# G785X.net
KiCad netlist of a schematic drawn in EAGLE
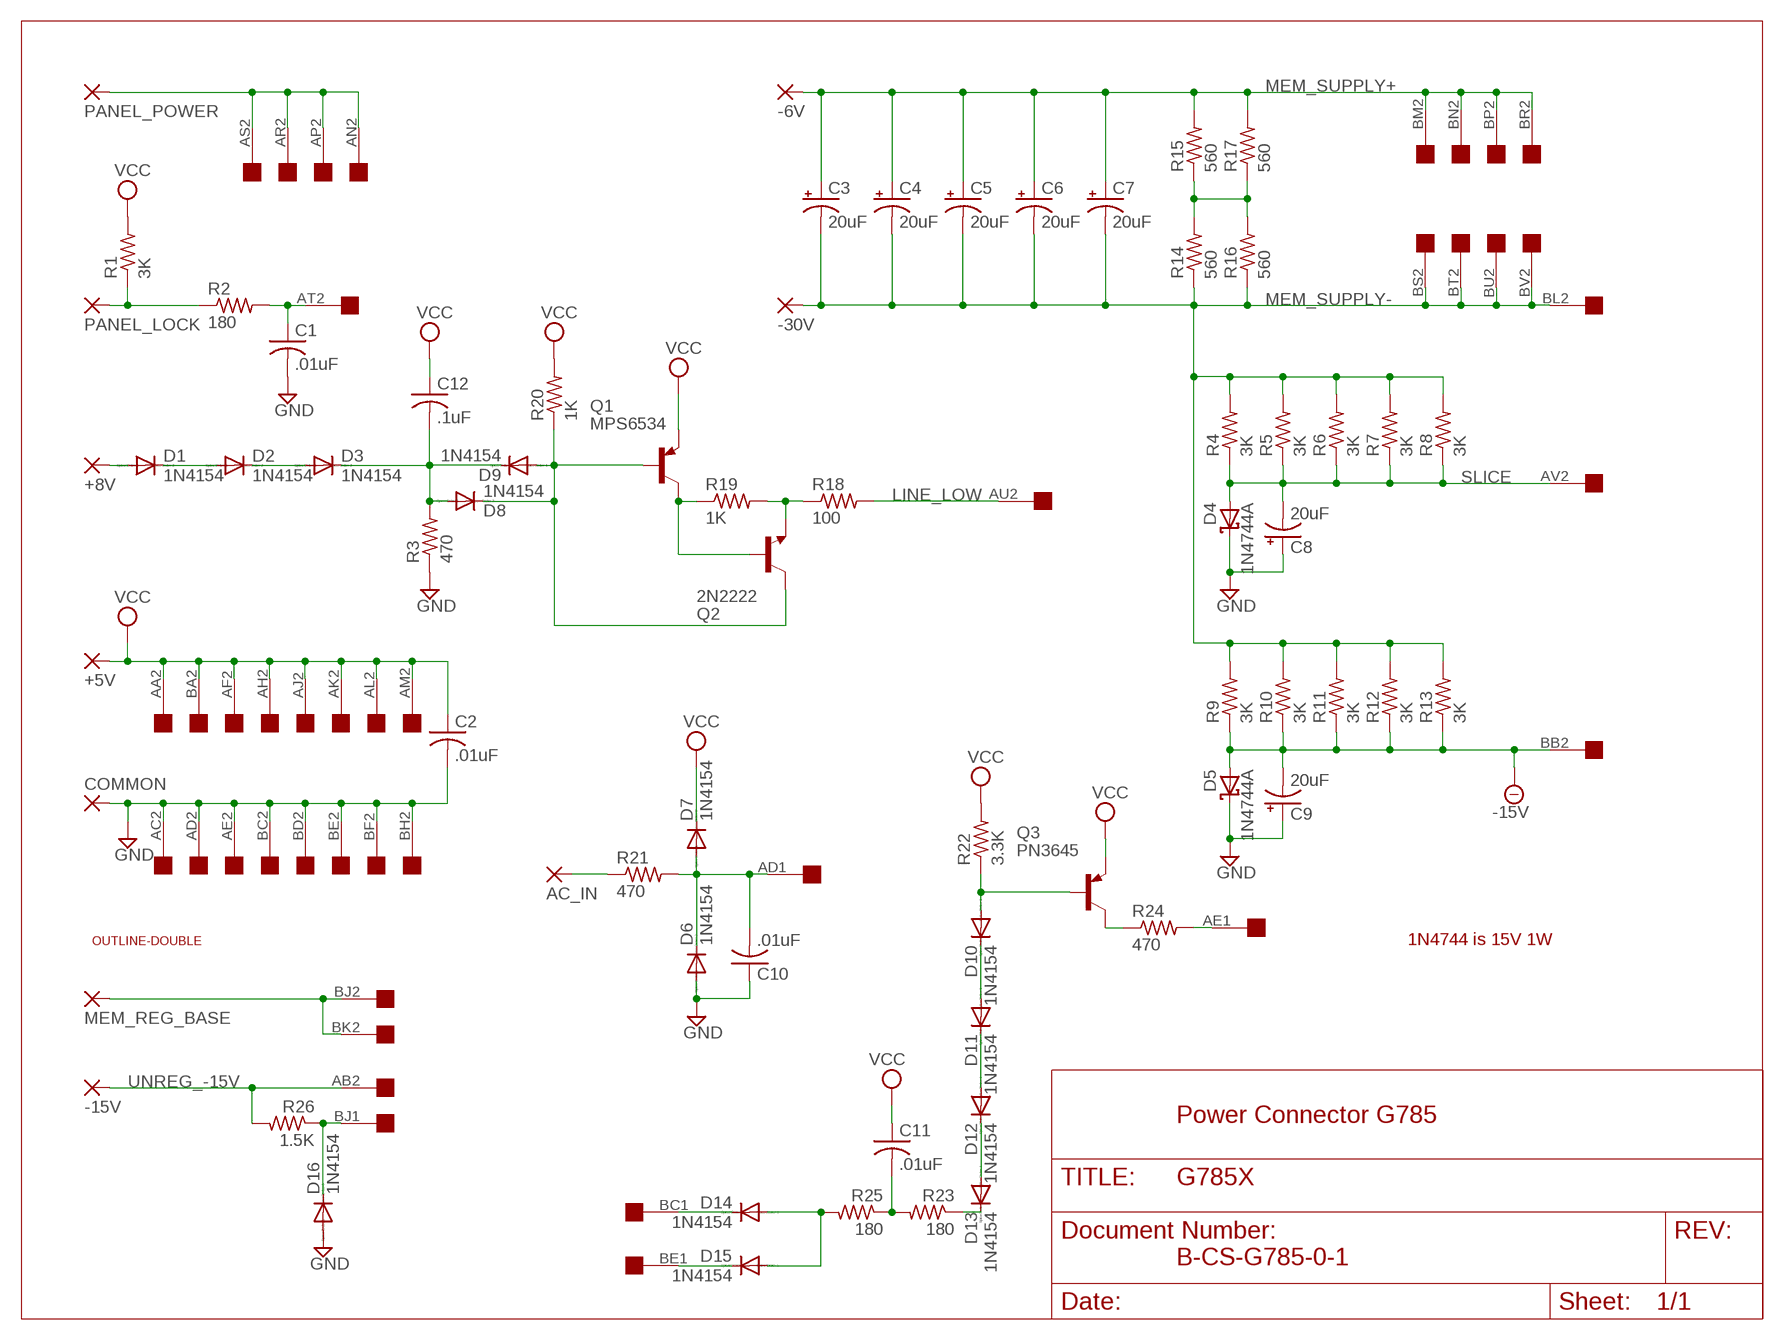
[diagram p0: schematic, sheet 1]

(export (version "E")
  (design (tool "Eeschema 10.0.6"))
  (components
    (comp (ref "+5V")
      (value "3,81/1,4")
      (footprint "eagle-import:3,81_1,4")
      (libsource (lib "eagle-import") (part "3,81/1,4"))
    )
    (comp (ref "+8V")
      (value "3,81/1,4")
      (footprint "eagle-import:3,81_1,4")
      (libsource (lib "eagle-import") (part "3,81/1,4"))
    )
    (comp (ref "-6V")
      (value "3,81/1,4")
      (footprint "eagle-import:3,81_1,4")
      (libsource (lib "eagle-import") (part "3,81/1,4"))
    )
    (comp (ref "-15V")
      (value "3,81/1,4")
      (footprint "eagle-import:3,81_1,4")
      (libsource (lib "eagle-import") (part "3,81/1,4"))
    )
    (comp (ref "-30V")
      (value "3,81/1,4")
      (footprint "eagle-import:3,81_1,4")
      (libsource (lib "eagle-import") (part "3,81/1,4"))
    )
    (comp (ref "AC_IN")
      (value "3,81/1,4")
      (footprint "eagle-import:3,81_1,4")
      (libsource (lib "eagle-import") (part "3,81/1,4"))
    )
    (comp (ref "C1")
      (value ".01uF")
      (footprint "eagle-import:C050-025X075")
      (libsource (lib "eagle-import") (part "C-US050-025X075"))
    )
    (comp (ref "C2")
      (value ".01uF")
      (footprint "eagle-import:C050-025X075")
      (libsource (lib "eagle-import") (part "C-US050-025X075"))
    )
    (comp (ref "C3")
      (value "20uF")
      (footprint "eagle-import:E25-9")
      (libsource (lib "eagle-import") (part "CPOL-USE25-9AXIAL"))
    )
    (comp (ref "C4")
      (value "20uF")
      (footprint "eagle-import:E25-9")
      (libsource (lib "eagle-import") (part "CPOL-USE25-9AXIAL"))
    )
    (comp (ref "C5")
      (value "20uF")
      (footprint "eagle-import:E25-9")
      (libsource (lib "eagle-import") (part "CPOL-USE25-9AXIAL"))
    )
    (comp (ref "C6")
      (value "20uF")
      (footprint "eagle-import:E25-9")
      (libsource (lib "eagle-import") (part "CPOL-USE25-9AXIAL"))
    )
    (comp (ref "C7")
      (value "20uF")
      (footprint "eagle-import:E25-9")
      (libsource (lib "eagle-import") (part "CPOL-USE25-9AXIAL"))
    )
    (comp (ref "C8")
      (value "20uF")
      (footprint "eagle-import:E25-9")
      (libsource (lib "eagle-import") (part "CPOL-USE25-9AXIAL"))
    )
    (comp (ref "C9")
      (value "20uF")
      (footprint "eagle-import:E25-9")
      (libsource (lib "eagle-import") (part "CPOL-USE25-9AXIAL"))
    )
    (comp (ref "C10")
      (value ".01uF")
      (footprint "eagle-import:C050-025X075")
      (libsource (lib "eagle-import") (part "C-US050-025X075"))
    )
    (comp (ref "C11")
      (value ".01uF")
      (footprint "eagle-import:C050-025X075")
      (libsource (lib "eagle-import") (part "C-US050-025X075"))
    )
    (comp (ref "C12")
      (value ".1uF")
      (footprint "eagle-import:C102-043X133")
      (libsource (lib "eagle-import") (part "C-US102-043X133"))
    )
    (comp (ref "COMMON")
      (value "3,81/1,4")
      (footprint "eagle-import:3,81_1,4")
      (libsource (lib "eagle-import") (part "3,81/1,4"))
    )
    (comp (ref "D1")
      (value "1N4154")
      (footprint "eagle-import:DO35-10")
      (libsource (lib "eagle-import") (part "1N4148DO35-10"))
    )
    (comp (ref "D2")
      (value "1N4154")
      (footprint "eagle-import:DO35-10")
      (libsource (lib "eagle-import") (part "1N4148DO35-10"))
    )
    (comp (ref "D3")
      (value "1N4154")
      (footprint "eagle-import:DO35-10")
      (libsource (lib "eagle-import") (part "1N4148DO35-10"))
    )
    (comp (ref "D4")
      (value "1N4744A")
      (footprint "eagle-import:DO35-10")
      (libsource (lib "eagle-import") (part "BAT42"))
    )
    (comp (ref "D5")
      (value "1N4744A")
      (footprint "eagle-import:DO35-10")
      (libsource (lib "eagle-import") (part "BAT42"))
    )
    (comp (ref "D6")
      (value "1N4154")
      (footprint "eagle-import:DO35-10")
      (libsource (lib "eagle-import") (part "1N4148DO35-10"))
    )
    (comp (ref "D7")
      (value "1N4154")
      (footprint "eagle-import:DO35-10")
      (libsource (lib "eagle-import") (part "1N4148DO35-10"))
    )
    (comp (ref "D8")
      (value "1N4154")
      (footprint "eagle-import:DO35-10")
      (libsource (lib "eagle-import") (part "1N4148DO35-10"))
    )
    (comp (ref "D9")
      (value "1N4154")
      (footprint "eagle-import:DO35-10")
      (libsource (lib "eagle-import") (part "1N4148DO35-10"))
    )
    (comp (ref "D10")
      (value "1N4154")
      (footprint "eagle-import:DO35-10")
      (libsource (lib "eagle-import") (part "1N4148DO35-10"))
    )
    (comp (ref "D11")
      (value "1N4154")
      (footprint "eagle-import:DO35-10")
      (libsource (lib "eagle-import") (part "1N4148DO35-10"))
    )
    (comp (ref "D12")
      (value "1N4154")
      (footprint "eagle-import:DO35-10")
      (libsource (lib "eagle-import") (part "1N4148DO35-10"))
    )
    (comp (ref "D13")
      (value "1N4154")
      (footprint "eagle-import:DO35-10")
      (libsource (lib "eagle-import") (part "1N4148DO35-10"))
    )
    (comp (ref "D14")
      (value "1N4154")
      (footprint "eagle-import:DO35-10")
      (libsource (lib "eagle-import") (part "1N4148DO35-10"))
    )
    (comp (ref "D15")
      (value "1N4154")
      (footprint "eagle-import:DO35-10")
      (libsource (lib "eagle-import") (part "1N4148DO35-10"))
    )
    (comp (ref "D16")
      (value "1N4154")
      (footprint "eagle-import:DO35-10")
      (libsource (lib "eagle-import") (part "1N4148DO35-10"))
    )
    (comp (ref "MEM_REG_BASE")
      (value "3,81/1,4")
      (footprint "eagle-import:3,81_1,4")
      (libsource (lib "eagle-import") (part "3,81/1,4"))
    )
    (comp (ref "PANEL_LOCK")
      (value "3,81/1,4")
      (footprint "eagle-import:3,81_1,4")
      (libsource (lib "eagle-import") (part "3,81/1,4"))
    )
    (comp (ref "PANEL_POWER")
      (value "3,81/1,4")
      (footprint "eagle-import:3,81_1,4")
      (libsource (lib "eagle-import") (part "3,81/1,4"))
    )
    (comp (ref "Q1")
      (value "MPS6534")
      (footprint "eagle-import:TO39")
      (libsource (lib "eagle-import") (part "2N2904"))
    )
    (comp (ref "Q2")
      (value "2N2222")
      (footprint "eagle-import:TO5")
      (libsource (lib "eagle-import") (part "2N2219"))
    )
    (comp (ref "Q3")
      (value "PN3645")
      (footprint "eagle-import:TO39")
      (libsource (lib "eagle-import") (part "2N2904"))
    )
    (comp (ref "R1")
      (value "3K")
      (footprint "eagle-import:0207_10")
      (libsource (lib "eagle-import") (part "R-US_0207/10"))
    )
    (comp (ref "R2")
      (value "180")
      (footprint "eagle-import:0207_10")
      (libsource (lib "eagle-import") (part "R-US_0207/10"))
    )
    (comp (ref "R3")
      (value "470")
      (footprint "eagle-import:0207_10")
      (libsource (lib "eagle-import") (part "R-US_0207/10"))
    )
    (comp (ref "R4")
      (value "3K")
      (footprint "eagle-import:0207_10")
      (libsource (lib "eagle-import") (part "R-US_0207/10"))
    )
    (comp (ref "R5")
      (value "3K")
      (footprint "eagle-import:0207_10")
      (libsource (lib "eagle-import") (part "R-US_0207/10"))
    )
    (comp (ref "R6")
      (value "3K")
      (footprint "eagle-import:0207_10")
      (libsource (lib "eagle-import") (part "R-US_0207/10"))
    )
    (comp (ref "R7")
      (value "3K")
      (footprint "eagle-import:0207_10")
      (libsource (lib "eagle-import") (part "R-US_0207/10"))
    )
    (comp (ref "R8")
      (value "3K")
      (footprint "eagle-import:0207_10")
      (libsource (lib "eagle-import") (part "R-US_0207/10"))
    )
    (comp (ref "R9")
      (value "3K")
      (footprint "eagle-import:0207_10")
      (libsource (lib "eagle-import") (part "R-US_0207/10"))
    )
    (comp (ref "R10")
      (value "3K")
      (footprint "eagle-import:0207_10")
      (libsource (lib "eagle-import") (part "R-US_0207/10"))
    )
    (comp (ref "R11")
      (value "3K")
      (footprint "eagle-import:0207_10")
      (libsource (lib "eagle-import") (part "R-US_0207/10"))
    )
    (comp (ref "R12")
      (value "3K")
      (footprint "eagle-import:0207_10")
      (libsource (lib "eagle-import") (part "R-US_0207/10"))
    )
    (comp (ref "R13")
      (value "3K")
      (footprint "eagle-import:0207_10")
      (libsource (lib "eagle-import") (part "R-US_0207/10"))
    )
    (comp (ref "R14")
      (value "560")
      (footprint "eagle-import:0207_10")
      (libsource (lib "eagle-import") (part "R-US_0207/10"))
    )
    (comp (ref "R15")
      (value "560")
      (footprint "eagle-import:0207_10")
      (libsource (lib "eagle-import") (part "R-US_0207/10"))
    )
    (comp (ref "R16")
      (value "560")
      (footprint "eagle-import:0207_10")
      (libsource (lib "eagle-import") (part "R-US_0207/10"))
    )
    (comp (ref "R17")
      (value "560")
      (footprint "eagle-import:0207_10")
      (libsource (lib "eagle-import") (part "R-US_0207/10"))
    )
    (comp (ref "R18")
      (value "100")
      (footprint "eagle-import:0207_10")
      (libsource (lib "eagle-import") (part "R-US_0207/10"))
    )
    (comp (ref "R19")
      (value "1K")
      (footprint "eagle-import:0207_10")
      (libsource (lib "eagle-import") (part "R-US_0207/10"))
    )
    (comp (ref "R20")
      (value "1K")
      (footprint "eagle-import:0207_10")
      (libsource (lib "eagle-import") (part "R-US_0207/10"))
    )
    (comp (ref "R21")
      (value "470")
      (footprint "eagle-import:0207_10")
      (libsource (lib "eagle-import") (part "R-US_0207/10"))
    )
    (comp (ref "R22")
      (value "3.3K")
      (footprint "eagle-import:0207_10")
      (libsource (lib "eagle-import") (part "R-US_0207/10"))
    )
    (comp (ref "R23")
      (value "180")
      (footprint "eagle-import:0207_10")
      (libsource (lib "eagle-import") (part "R-US_0207/10"))
    )
    (comp (ref "R24")
      (value "470")
      (footprint "eagle-import:0207_10")
      (libsource (lib "eagle-import") (part "R-US_0207/10"))
    )
    (comp (ref "R25")
      (value "180")
      (footprint "eagle-import:0207_10")
      (libsource (lib "eagle-import") (part "R-US_0207/10"))
    )
    (comp (ref "R26")
      (value "1.5K")
      (footprint "eagle-import:0207_10")
      (libsource (lib "eagle-import") (part "R-US_0207/10"))
    )
    (comp (ref "U$1")
      (value "DOUBLE")
      (footprint "eagle-import:EDGE-CON4")
      (libsource (lib "eagle-import") (part "DOUBLE"))
    )
    (comp (ref "U$2")
      (value "OUTLINE-DOUBLE")
      (footprint "eagle-import:DOUBLE")
      (libsource (lib "eagle-import") (part "OUTLINE-DOUBLE"))
    )
  )
  (nets
    (net (code "1") (name "-15V") (class "Default")
      (node (ref "C9") (pin "-") (pinfunction "-_-") (pintype "passive"))
      (node (ref "D5") (pin "A") (pinfunction "A_A") (pintype "passive"))
      (node (ref "R10") (pin "1") (pinfunction "1_1") (pintype "passive"))
      (node (ref "R11") (pin "1") (pinfunction "1_1") (pintype "passive"))
      (node (ref "R12") (pin "1") (pinfunction "1_1") (pintype "passive"))
      (node (ref "R13") (pin "1") (pinfunction "1_1") (pintype "passive"))
      (node (ref "R9") (pin "1") (pinfunction "1_1") (pintype "passive"))
      (node (ref "U$1") (pin "BB2") (pinfunction "1_BB2") (pintype "bidirectional"))
    )
    (net (code "2") (name "/LINE_LOW") (class "Default")
      (node (ref "R18") (pin "2") (pinfunction "2_2") (pintype "passive"))
      (node (ref "U$1") (pin "AU2") (pinfunction "1_AU2") (pintype "bidirectional"))
    )
    (net (code "3") (name "/MEM_SUPPLY+") (class "Default")
      (node (ref "-6V") (pin "1") (pinfunction "P_1") (pintype "passive"))
      (node (ref "C3") (pin "+") (pinfunction "+_+") (pintype "passive"))
      (node (ref "C4") (pin "+") (pinfunction "+_+") (pintype "passive"))
      (node (ref "C5") (pin "+") (pinfunction "+_+") (pintype "passive"))
      (node (ref "C6") (pin "+") (pinfunction "+_+") (pintype "passive"))
      (node (ref "C7") (pin "+") (pinfunction "+_+") (pintype "passive"))
      (node (ref "R15") (pin "2") (pinfunction "2_2") (pintype "passive"))
      (node (ref "R17") (pin "2") (pinfunction "2_2") (pintype "passive"))
      (node (ref "U$1") (pin "BM2") (pinfunction "1_BM2") (pintype "bidirectional"))
      (node (ref "U$1") (pin "BN2") (pinfunction "1_BN2") (pintype "bidirectional"))
      (node (ref "U$1") (pin "BP2") (pinfunction "1_BP2") (pintype "bidirectional"))
      (node (ref "U$1") (pin "BR2") (pinfunction "1_BR2") (pintype "bidirectional"))
    )
    (net (code "4") (name "/MEM_SUPPLY-") (class "Default")
      (node (ref "-30V") (pin "1") (pinfunction "P_1") (pintype "passive"))
      (node (ref "C3") (pin "-") (pinfunction "-_-") (pintype "passive"))
      (node (ref "C4") (pin "-") (pinfunction "-_-") (pintype "passive"))
      (node (ref "C5") (pin "-") (pinfunction "-_-") (pintype "passive"))
      (node (ref "C6") (pin "-") (pinfunction "-_-") (pintype "passive"))
      (node (ref "C7") (pin "-") (pinfunction "-_-") (pintype "passive"))
      (node (ref "R10") (pin "2") (pinfunction "2_2") (pintype "passive"))
      (node (ref "R11") (pin "2") (pinfunction "2_2") (pintype "passive"))
      (node (ref "R12") (pin "2") (pinfunction "2_2") (pintype "passive"))
      (node (ref "R13") (pin "2") (pinfunction "2_2") (pintype "passive"))
      (node (ref "R14") (pin "1") (pinfunction "1_1") (pintype "passive"))
      (node (ref "R16") (pin "1") (pinfunction "1_1") (pintype "passive"))
      (node (ref "R4") (pin "2") (pinfunction "2_2") (pintype "passive"))
      (node (ref "R5") (pin "2") (pinfunction "2_2") (pintype "passive"))
      (node (ref "R6") (pin "2") (pinfunction "2_2") (pintype "passive"))
      (node (ref "R7") (pin "2") (pinfunction "2_2") (pintype "passive"))
      (node (ref "R8") (pin "2") (pinfunction "2_2") (pintype "passive"))
      (node (ref "R9") (pin "2") (pinfunction "2_2") (pintype "passive"))
      (node (ref "U$1") (pin "BL2") (pinfunction "1_BL2") (pintype "bidirectional"))
      (node (ref "U$1") (pin "BS2") (pinfunction "1_BS2") (pintype "bidirectional"))
      (node (ref "U$1") (pin "BT2") (pinfunction "1_BT2") (pintype "bidirectional"))
      (node (ref "U$1") (pin "BU2") (pinfunction "1_BU2") (pintype "bidirectional"))
      (node (ref "U$1") (pin "BV2") (pinfunction "1_BV2") (pintype "bidirectional"))
    )
    (net (code "5") (name "/SLICE") (class "Default")
      (node (ref "C8") (pin "-") (pinfunction "-_-") (pintype "passive"))
      (node (ref "D4") (pin "A") (pinfunction "A_A") (pintype "passive"))
      (node (ref "R4") (pin "1") (pinfunction "1_1") (pintype "passive"))
      (node (ref "R5") (pin "1") (pinfunction "1_1") (pintype "passive"))
      (node (ref "R6") (pin "1") (pinfunction "1_1") (pintype "passive"))
      (node (ref "R7") (pin "1") (pinfunction "1_1") (pintype "passive"))
      (node (ref "R8") (pin "1") (pinfunction "1_1") (pintype "passive"))
      (node (ref "U$1") (pin "AV2") (pinfunction "1_AV2") (pintype "bidirectional"))
    )
    (net (code "6") (name "/UNREG_-15V") (class "Default")
      (node (ref "-15V") (pin "1") (pinfunction "P_1") (pintype "passive"))
      (node (ref "R26") (pin "2") (pinfunction "2_2") (pintype "passive"))
      (node (ref "U$1") (pin "AB2") (pinfunction "1_AB2") (pintype "bidirectional"))
    )
    (net (code "7") (name "GND") (class "Default")
      (node (ref "C1") (pin "2") (pinfunction "2_2") (pintype "passive"))
      (node (ref "C10") (pin "1") (pinfunction "1_1") (pintype "passive"))
      (node (ref "C2") (pin "2") (pinfunction "2_2") (pintype "passive"))
      (node (ref "C8") (pin "+") (pinfunction "+_+") (pintype "passive"))
      (node (ref "C9") (pin "+") (pinfunction "+_+") (pintype "passive"))
      (node (ref "COMMON") (pin "1") (pinfunction "P_1") (pintype "passive"))
      (node (ref "D16") (pin "A") (pinfunction "A_A") (pintype "passive"))
      (node (ref "D4") (pin "C") (pinfunction "C_C") (pintype "passive"))
      (node (ref "D5") (pin "C") (pinfunction "C_C") (pintype "passive"))
      (node (ref "D6") (pin "A") (pinfunction "A_A") (pintype "passive"))
      (node (ref "R3") (pin "1") (pinfunction "1_1") (pintype "passive"))
      (node (ref "U$1") (pin "AC2") (pinfunction "1_AC2") (pintype "bidirectional"))
      (node (ref "U$1") (pin "AD2") (pinfunction "1_AD2") (pintype "bidirectional"))
      (node (ref "U$1") (pin "AE2") (pinfunction "1_AE2") (pintype "bidirectional"))
      (node (ref "U$1") (pin "BC2") (pinfunction "1_BC2") (pintype "bidirectional"))
      (node (ref "U$1") (pin "BD2") (pinfunction "1_BD2") (pintype "bidirectional"))
      (node (ref "U$1") (pin "BE2") (pinfunction "1_BE2") (pintype "bidirectional"))
      (node (ref "U$1") (pin "BF2") (pinfunction "1_BF2") (pintype "bidirectional"))
      (node (ref "U$1") (pin "BH2") (pinfunction "1_BH2") (pintype "bidirectional"))
    )
    (net (code "8") (name "Net-(+8V-P)") (class "Default")
      (node (ref "+8V") (pin "1") (pinfunction "P_1") (pintype "passive"))
      (node (ref "D1") (pin "A") (pinfunction "A_A") (pintype "passive"))
    )
    (net (code "9") (name "Net-(AC_IN-P)") (class "Default")
      (node (ref "AC_IN") (pin "1") (pinfunction "P_1") (pintype "passive"))
      (node (ref "R21") (pin "1") (pinfunction "1_1") (pintype "passive"))
    )
    (net (code "10") (name "Net-(C11-Pad2)") (class "Default")
      (node (ref "C11") (pin "2") (pinfunction "2_2") (pintype "passive"))
      (node (ref "R23") (pin "2") (pinfunction "2_2") (pintype "passive"))
      (node (ref "R25") (pin "1") (pinfunction "1_1") (pintype "passive"))
    )
    (net (code "11") (name "Net-(C12-Pad2)") (class "Default")
      (node (ref "C12") (pin "2") (pinfunction "2_2") (pintype "passive"))
      (node (ref "D3") (pin "C") (pinfunction "C_C") (pintype "passive"))
      (node (ref "D8") (pin "A") (pinfunction "A_A") (pintype "passive"))
      (node (ref "D9") (pin "C") (pinfunction "C_C") (pintype "passive"))
      (node (ref "R3") (pin "2") (pinfunction "2_2") (pintype "passive"))
    )
    (net (code "12") (name "Net-(D1-PadC)") (class "Default")
      (node (ref "D1") (pin "C") (pinfunction "C_C") (pintype "passive"))
      (node (ref "D2") (pin "A") (pinfunction "A_A") (pintype "passive"))
    )
    (net (code "13") (name "Net-(D2-PadC)") (class "Default")
      (node (ref "D2") (pin "C") (pinfunction "C_C") (pintype "passive"))
      (node (ref "D3") (pin "A") (pinfunction "A_A") (pintype "passive"))
    )
    (net (code "14") (name "Net-(D10-PadC)") (class "Default")
      (node (ref "D10") (pin "C") (pinfunction "C_C") (pintype "passive"))
      (node (ref "D11") (pin "A") (pinfunction "A_A") (pintype "passive"))
    )
    (net (code "15") (name "Net-(D11-PadC)") (class "Default")
      (node (ref "D11") (pin "C") (pinfunction "C_C") (pintype "passive"))
      (node (ref "D12") (pin "A") (pinfunction "A_A") (pintype "passive"))
    )
    (net (code "16") (name "Net-(D12-PadC)") (class "Default")
      (node (ref "D12") (pin "C") (pinfunction "C_C") (pintype "passive"))
      (node (ref "D13") (pin "A") (pinfunction "A_A") (pintype "passive"))
    )
    (net (code "17") (name "Net-(D13-PadC)") (class "Default")
      (node (ref "D13") (pin "C") (pinfunction "C_C") (pintype "passive"))
      (node (ref "R23") (pin "1") (pinfunction "1_1") (pintype "passive"))
    )
    (net (code "18") (name "Net-(D14-PadA)") (class "Default")
      (node (ref "D14") (pin "A") (pinfunction "A_A") (pintype "passive"))
      (node (ref "D15") (pin "A") (pinfunction "A_A") (pintype "passive"))
      (node (ref "R25") (pin "2") (pinfunction "2_2") (pintype "passive"))
    )
    (net (code "19") (name "Net-(MEM_REG_BASE-P)") (class "Default")
      (node (ref "MEM_REG_BASE") (pin "1") (pinfunction "P_1") (pintype "passive"))
      (node (ref "U$1") (pin "BJ2") (pinfunction "1_BJ2") (pintype "bidirectional"))
      (node (ref "U$1") (pin "BK2") (pinfunction "1_BK2") (pintype "bidirectional"))
    )
    (net (code "20") (name "Net-(PANEL_LOCK-P)") (class "Default")
      (node (ref "PANEL_LOCK") (pin "1") (pinfunction "P_1") (pintype "passive"))
      (node (ref "R1") (pin "1") (pinfunction "1_1") (pintype "passive"))
      (node (ref "R2") (pin "1") (pinfunction "1_1") (pintype "passive"))
    )
    (net (code "21") (name "Net-(PANEL_POWER-P)") (class "Default")
      (node (ref "PANEL_POWER") (pin "1") (pinfunction "P_1") (pintype "passive"))
      (node (ref "U$1") (pin "AN2") (pinfunction "1_AN2") (pintype "bidirectional"))
      (node (ref "U$1") (pin "AP2") (pinfunction "1_AP2") (pintype "bidirectional"))
      (node (ref "U$1") (pin "AR2") (pinfunction "1_AR2") (pintype "bidirectional"))
      (node (ref "U$1") (pin "AS2") (pinfunction "1_AS2") (pintype "bidirectional"))
    )
    (net (code "22") (name "Net-(Q1-B)") (class "Default")
      (node (ref "D8") (pin "C") (pinfunction "C_C") (pintype "passive"))
      (node (ref "D9") (pin "A") (pinfunction "A_A") (pintype "passive"))
      (node (ref "Q1") (pin "2") (pinfunction "B_2") (pintype "passive"))
      (node (ref "Q2") (pin "3") (pinfunction "C_3") (pintype "passive"))
      (node (ref "R20") (pin "1") (pinfunction "1_1") (pintype "passive"))
    )
    (net (code "23") (name "Net-(Q1-C)") (class "Default")
      (node (ref "Q1") (pin "3") (pinfunction "C_3") (pintype "passive"))
      (node (ref "Q2") (pin "2") (pinfunction "B_2") (pintype "passive"))
      (node (ref "R19") (pin "1") (pinfunction "1_1") (pintype "passive"))
    )
    (net (code "24") (name "Net-(Q2-E)") (class "Default")
      (node (ref "Q2") (pin "1") (pinfunction "E_1") (pintype "passive"))
      (node (ref "R18") (pin "1") (pinfunction "1_1") (pintype "passive"))
      (node (ref "R19") (pin "2") (pinfunction "2_2") (pintype "passive"))
    )
    (net (code "25") (name "Net-(Q3-B)") (class "Default")
      (node (ref "D10") (pin "A") (pinfunction "A_A") (pintype "passive"))
      (node (ref "Q3") (pin "2") (pinfunction "B_2") (pintype "passive"))
      (node (ref "R22") (pin "1") (pinfunction "1_1") (pintype "passive"))
    )
    (net (code "26") (name "Net-(Q3-C)") (class "Default")
      (node (ref "Q3") (pin "3") (pinfunction "C_3") (pintype "passive"))
      (node (ref "R24") (pin "1") (pinfunction "1_1") (pintype "passive"))
    )
    (net (code "27") (name "Net-(R14-Pad2)") (class "Default")
      (node (ref "R14") (pin "2") (pinfunction "2_2") (pintype "passive"))
      (node (ref "R15") (pin "1") (pinfunction "1_1") (pintype "passive"))
      (node (ref "R16") (pin "2") (pinfunction "2_2") (pintype "passive"))
      (node (ref "R17") (pin "1") (pinfunction "1_1") (pintype "passive"))
    )
    (net (code "28") (name "Net-(U$1AF-1)") (class "Default")
      (node (ref "C1") (pin "1") (pinfunction "1_1") (pintype "passive"))
      (node (ref "R2") (pin "2") (pinfunction "2_2") (pintype "passive"))
      (node (ref "U$1") (pin "AT2") (pinfunction "1_AT2") (pintype "bidirectional"))
    )
    (net (code "29") (name "Net-(U$1AO-1)") (class "Default")
      (node (ref "D14") (pin "C") (pinfunction "C_C") (pintype "passive"))
      (node (ref "U$1") (pin "BC1") (pinfunction "1_BC1") (pintype "bidirectional"))
    )
    (net (code "30") (name "Net-(U$1AS-1)") (class "Default")
      (node (ref "D15") (pin "C") (pinfunction "C_C") (pintype "passive"))
      (node (ref "U$1") (pin "BE1") (pinfunction "1_BE1") (pintype "bidirectional"))
    )
    (net (code "31") (name "Net-(U$1AY-1)") (class "Default")
      (node (ref "D16") (pin "C") (pinfunction "C_C") (pintype "passive"))
      (node (ref "R26") (pin "1") (pinfunction "1_1") (pintype "passive"))
      (node (ref "U$1") (pin "BJ1") (pinfunction "1_BJ1") (pintype "bidirectional"))
    )
    (net (code "32") (name "Net-(U$1G-1)") (class "Default")
      (node (ref "C10") (pin "2") (pinfunction "2_2") (pintype "passive"))
      (node (ref "D6") (pin "C") (pinfunction "C_C") (pintype "passive"))
      (node (ref "D7") (pin "A") (pinfunction "A_A") (pintype "passive"))
      (node (ref "R21") (pin "2") (pinfunction "2_2") (pintype "passive"))
      (node (ref "U$1") (pin "AD1") (pinfunction "1_AD1") (pintype "bidirectional"))
    )
    (net (code "33") (name "Net-(U$1I-1)") (class "Default")
      (node (ref "R24") (pin "2") (pinfunction "2_2") (pintype "passive"))
      (node (ref "U$1") (pin "AE1") (pinfunction "1_AE1") (pintype "bidirectional"))
    )
    (net (code "34") (name "VCC") (class "Default")
      (node (ref "+5V") (pin "1") (pinfunction "P_1") (pintype "passive"))
      (node (ref "C11") (pin "1") (pinfunction "1_1") (pintype "passive"))
      (node (ref "C12") (pin "1") (pinfunction "1_1") (pintype "passive"))
      (node (ref "C2") (pin "1") (pinfunction "1_1") (pintype "passive"))
      (node (ref "D7") (pin "C") (pinfunction "C_C") (pintype "passive"))
      (node (ref "Q1") (pin "1") (pinfunction "E_1") (pintype "passive"))
      (node (ref "Q3") (pin "1") (pinfunction "E_1") (pintype "passive"))
      (node (ref "R1") (pin "2") (pinfunction "2_2") (pintype "passive"))
      (node (ref "R20") (pin "2") (pinfunction "2_2") (pintype "passive"))
      (node (ref "R22") (pin "2") (pinfunction "2_2") (pintype "passive"))
      (node (ref "U$1") (pin "AA2") (pinfunction "1_AA2") (pintype "bidirectional"))
      (node (ref "U$1") (pin "AF2") (pinfunction "1_AF2") (pintype "bidirectional"))
      (node (ref "U$1") (pin "AH2") (pinfunction "1_AH2") (pintype "bidirectional"))
      (node (ref "U$1") (pin "AJ2") (pinfunction "1_AJ2") (pintype "bidirectional"))
      (node (ref "U$1") (pin "AK2") (pinfunction "1_AK2") (pintype "bidirectional"))
      (node (ref "U$1") (pin "AL2") (pinfunction "1_AL2") (pintype "bidirectional"))
      (node (ref "U$1") (pin "AM2") (pinfunction "1_AM2") (pintype "bidirectional"))
      (node (ref "U$1") (pin "BA2") (pinfunction "1_BA2") (pintype "bidirectional"))
    )
  )
)
